# Power_Sheet.net
KiCad netlist of a schematic drawn in Altium Designer
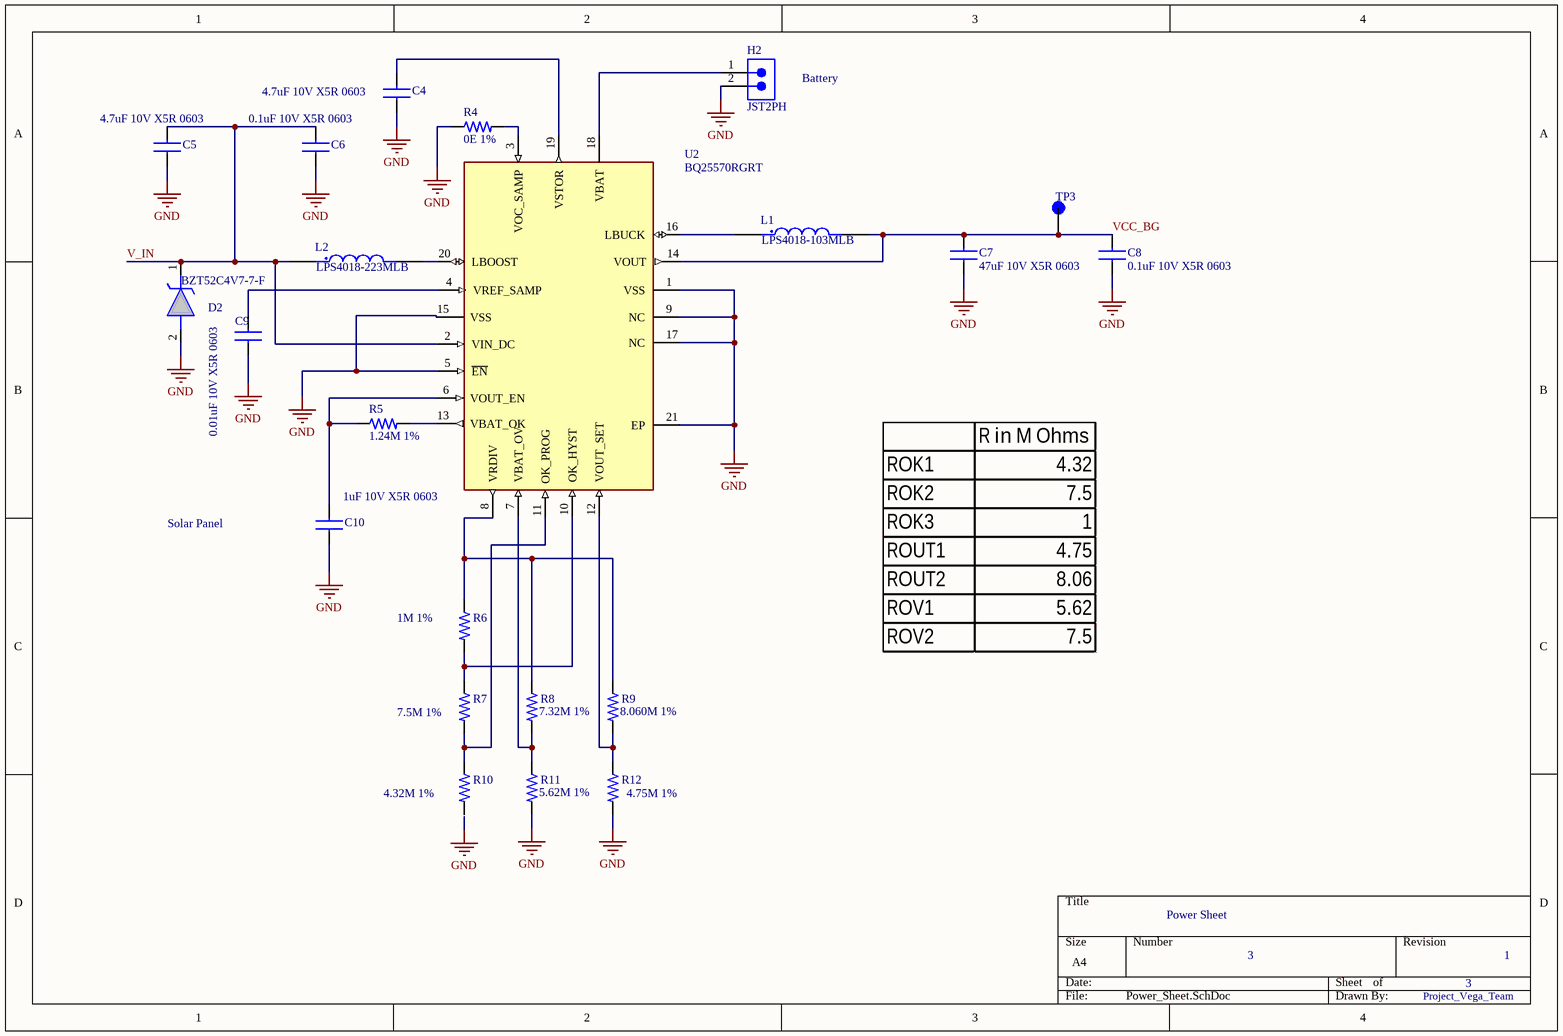
[diagram p0: Power_Sheet.SchDoc]

(export (version "E")
  (design (tool "Eeschema 10.0.6"))
  (components
    (comp (ref "C4")
      (value "4.7uF 10V X5R 0603")
      (footprint "CAP_0603_1MM")
      (description "CAP CER 22UF 10V X5R 0603")
      (fields
        (field (name "MANUFACTURER") "Murata")
        (field (name "MANUFACTURER PART NUMBER") "GRM188R61A226ME15D")
      )
      (libsource (lib "LPEDT_Parts") (part "GRM188R61A226ME15D"))
    )
    (comp (ref "C5")
      (value "4.7uF 10V X5R 0603")
      (footprint "CAP_0603_1MM")
      (description "CAP CER 22UF 10V X5R 0603")
      (fields
        (field (name "MANUFACTURER") "Murata")
        (field (name "MANUFACTURER PART NUMBER") "GRM188R61A226ME15D")
      )
      (libsource (lib "LPEDT_Parts") (part "GRM188R61A226ME15D"))
    )
    (comp (ref "C6")
      (value "0.1uF 10V X5R 0603")
      (footprint "CAP_0603_1MM")
      (description "CAP CER 22UF 10V X5R 0603")
      (fields
        (field (name "MANUFACTURER") "Murata")
        (field (name "MANUFACTURER PART NUMBER") "GRM188R61A226ME15D")
      )
      (libsource (lib "LPEDT_Parts") (part "GRM188R61A226ME15D"))
    )
    (comp (ref "C7")
      (value "47uF 10V X5R 0603")
      (footprint "CAP_0603_1MM")
      (description "CAP CER 22UF 10V X5R 0603")
      (fields
        (field (name "MANUFACTURER") "Murata")
        (field (name "MANUFACTURER PART NUMBER") "GRM188R61A226ME15D")
      )
      (libsource (lib "LPEDT_Parts") (part "GRM188R61A226ME15D"))
    )
    (comp (ref "C8")
      (value "0.1uF 10V X5R 0603")
      (footprint "CAP_0603_1MM")
      (description "CAP CER 22UF 10V X5R 0603")
      (fields
        (field (name "MANUFACTURER") "Murata")
        (field (name "MANUFACTURER PART NUMBER") "GRM188R61A226ME15D")
      )
      (libsource (lib "LPEDT_Parts") (part "GRM188R61A226ME15D"))
    )
    (comp (ref "C9")
      (value "0.01uF 10V X5R 0603")
      (footprint "CAP_0603_1MM")
      (description "CAP CER 22UF 10V X5R 0603")
      (fields
        (field (name "MANUFACTURER") "Murata")
        (field (name "MANUFACTURER PART NUMBER") "GRM188R61A226ME15D")
      )
      (libsource (lib "LPEDT_Parts") (part "GRM188R61A226ME15D"))
    )
    (comp (ref "C10")
      (value "1uF 10V X5R 0603")
      (footprint "CAP_0603_1MM")
      (description "CAP CER 22UF 10V X5R 0603")
      (fields
        (field (name "MANUFACTURER") "Murata")
        (field (name "MANUFACTURER PART NUMBER") "GRM188R61A226ME15D")
      )
      (libsource (lib "LPEDT_Parts") (part "GRM188R61A226ME15D"))
    )
    (comp (ref "D2")
      (value "BZT52C4V7-7-F")
      (footprint "SOD3716X145N")
      (description "Diodes Inc BZT52C4V7-7-F Zener Diode, 4.7V 7% 500 mW SMT 2-Pin SOD-123")
      (fields (field (name "MOUSER PART NUMBER") "621-BZT52C4V7-F"))
      (libsource (lib "BZT52C4V7-7-F") (part "BZT52C4V7-7-F"))
    )
    (comp (ref "H2")
      (value "JST2PH")
      (footprint "JST_B2B-PH-K-S(LF)(SN)")
      (description "Connector Header Through Hole 2 position 0.079\" (2.00mm)")
      (fields (field (name "MANUFACTURER") "JST") (field (name "MANUFACTURER PART NUMBER") "B2B-PH-K-S"))
      (libsource (lib "Connectors") (part "JST2PH"))
    )
    (comp (ref "L1")
      (value "LPS4018-103MLB")
      (footprint "IND_LPS4018-223MRC")
      (description "22 µH Shielded Drum Core Inductor 650 mA 360mOhm Max Nonstandard")
      (fields (field (name "MF") "Coilcraft") (field (name "MP") "LPS4018-223MRC"))
      (libsource (lib "LPS4018-223MRC") (part "LPS4018-223MRC"))
    )
    (comp (ref "L2")
      (value "LPS4018-223MLB")
      (footprint "IND_LPS4018-223MRC")
      (description "22 µH Shielded Drum Core Inductor 650 mA 360mOhm Max Nonstandard")
      (fields (field (name "MF") "Coilcraft") (field (name "MP") "LPS4018-223MRC"))
      (libsource (lib "LPS4018-223MRC") (part "LPS4018-223MRC"))
    )
    (comp (ref "R4")
      (value "0E 1%")
      (footprint "RES_0603_1608X06")
      (description "SMD Chip Resistor, 316 kOhm, ± 1%, 100 mW, 0603 [1608 Metric], Thick Film, General Purpose")
      (fields
        (field (name "MANUFACTURER") "Yageo")
        (field (name "MANUFACTURER PART NUMBER") "RC0603FR-07316KL")
      )
      (libsource (lib "LPEDT_Parts") (part "RC0603FR-07316KL"))
    )
    (comp (ref "R5")
      (value "1.24M 1%")
      (footprint "RES_0603_1608X06")
      (description "SMD Chip Resistor, 316 kOhm, ± 1%, 100 mW, 0603 [1608 Metric], Thick Film, General Purpose")
      (fields
        (field (name "MANUFACTURER") "Yageo")
        (field (name "MANUFACTURER PART NUMBER") "RC0603FR-07316KL")
      )
      (libsource (lib "LPEDT_Parts") (part "RC0603FR-07316KL"))
    )
    (comp (ref "R6")
      (value "1M 1%")
      (footprint "RES_0603_1608X06")
      (description "SMD Chip Resistor, 316 kOhm, ± 1%, 100 mW, 0603 [1608 Metric], Thick Film, General Purpose")
      (fields
        (field (name "MANUFACTURER") "Yageo")
        (field (name "MANUFACTURER PART NUMBER") "RC0603FR-07316KL")
      )
      (libsource (lib "LPEDT_Parts") (part "RC0603FR-07316KL"))
    )
    (comp (ref "R7")
      (value "7.5M 1%")
      (footprint "RES_0603_1608X06")
      (description "SMD Chip Resistor, 316 kOhm, ± 1%, 100 mW, 0603 [1608 Metric], Thick Film, General Purpose")
      (fields
        (field (name "MANUFACTURER") "Yageo")
        (field (name "MANUFACTURER PART NUMBER") "RC0603FR-07316KL")
      )
      (libsource (lib "LPEDT_Parts") (part "RC0603FR-07316KL"))
    )
    (comp (ref "R8")
      (value "7.32M 1%")
      (footprint "RES_0603_1608X06")
      (description "SMD Chip Resistor, 316 kOhm, ± 1%, 100 mW, 0603 [1608 Metric], Thick Film, General Purpose")
      (fields
        (field (name "MANUFACTURER") "Yageo")
        (field (name "MANUFACTURER PART NUMBER") "RC0603FR-07316KL")
      )
      (libsource (lib "LPEDT_Parts") (part "RC0603FR-07316KL"))
    )
    (comp (ref "R9")
      (value "8.060M 1%")
      (footprint "RES_0603_1608X06")
      (description "SMD Chip Resistor, 316 kOhm, ± 1%, 100 mW, 0603 [1608 Metric], Thick Film, General Purpose")
      (fields
        (field (name "MANUFACTURER") "Yageo")
        (field (name "MANUFACTURER PART NUMBER") "RC0603FR-07316KL")
      )
      (libsource (lib "LPEDT_Parts") (part "RC0603FR-07316KL"))
    )
    (comp (ref "R10")
      (value "4.32M 1%")
      (footprint "RES_0603_1608X06")
      (description "SMD Chip Resistor, 316 kOhm, ± 1%, 100 mW, 0603 [1608 Metric], Thick Film, General Purpose")
      (fields
        (field (name "MANUFACTURER") "Yageo")
        (field (name "MANUFACTURER PART NUMBER") "RC0603FR-07316KL")
      )
      (libsource (lib "LPEDT_Parts") (part "RC0603FR-07316KL"))
    )
    (comp (ref "R11")
      (value "5.62M 1%")
      (footprint "RES_0603_1608X06")
      (description "SMD Chip Resistor, 316 kOhm, ± 1%, 100 mW, 0603 [1608 Metric], Thick Film, General Purpose")
      (fields
        (field (name "MANUFACTURER") "Yageo")
        (field (name "MANUFACTURER PART NUMBER") "RC0603FR-07316KL")
      )
      (libsource (lib "LPEDT_Parts") (part "RC0603FR-07316KL"))
    )
    (comp (ref "R12")
      (value "4.75M 1%")
      (footprint "RES_0603_1608X06")
      (description "SMD Chip Resistor, 316 kOhm, ± 1%, 100 mW, 0603 [1608 Metric], Thick Film, General Purpose")
      (fields
        (field (name "MANUFACTURER") "Yageo")
        (field (name "MANUFACTURER PART NUMBER") "RC0603FR-07316KL")
      )
      (libsource (lib "LPEDT_Parts") (part "RC0603FR-07316KL"))
    )
    (comp (ref "TP3")
      (value "Test_point")
      (footprint "TP")
      (description "SMT Test Point- Mininature-1000 pc Reels")
      (fields (field (name "MP") "5019") (field (name "MF") "Keystone Electronics"))
      (libsource (lib "Project_Vega") (part "Test_point"))
    )
    (comp (ref "U2")
      (value "BQ25570RGRT")
      (footprint "QFN50P350X350X100-21N")
      (fields (field (name "MF") "Texas Instruments"))
      (libsource (lib "Project_Vega") (part "BQ25570RGRT"))
    )
  )
  (nets
    (net (code "1") (name "/VCC_BG") (class "Default")
      (node (ref "C7") (pin "2") (pinfunction "2_2") (pintype "passive"))
      (node (ref "C8") (pin "2") (pinfunction "2_2") (pintype "passive"))
      (node (ref "L1") (pin "2") (pinfunction "2_2") (pintype "passive"))
      (node (ref "TP3") (pin "TP") (pinfunction "TP_TP") (pintype "passive"))
      (node (ref "U2") (pin "14") (pinfunction "VOUT_14") (pintype "output"))
    )
    (net (code "2") (name "/V_IN") (class "Default")
      (node (ref "C5") (pin "2") (pinfunction "2_2") (pintype "passive"))
      (node (ref "C6") (pin "2") (pinfunction "2_2") (pintype "passive"))
      (node (ref "D2") (pin "1") (pinfunction "K_1") (pintype "passive"))
      (node (ref "L2") (pin "1") (pinfunction "1_1") (pintype "passive"))
      (node (ref "U2") (pin "2") (pinfunction "VIN_DC_2") (pintype "input"))
    )
    (net (code "3") (name "GND") (class "Default")
      (node (ref "C10") (pin "1") (pinfunction "1_1") (pintype "passive"))
      (node (ref "C4") (pin "1") (pinfunction "1_1") (pintype "passive"))
      (node (ref "C5") (pin "1") (pinfunction "1_1") (pintype "passive"))
      (node (ref "C6") (pin "1") (pinfunction "1_1") (pintype "passive"))
      (node (ref "C7") (pin "1") (pinfunction "1_1") (pintype "passive"))
      (node (ref "C8") (pin "1") (pinfunction "1_1") (pintype "passive"))
      (node (ref "C9") (pin "1") (pinfunction "1_1") (pintype "passive"))
      (node (ref "D2") (pin "2") (pinfunction "A_2") (pintype "passive"))
      (node (ref "H2") (pin "2") (pinfunction "2_2") (pintype "passive"))
      (node (ref "R11") (pin "2") (pinfunction "2_2") (pintype "passive"))
      (node (ref "R12") (pin "2") (pinfunction "2_2") (pintype "passive"))
      (node (ref "R4") (pin "1") (pinfunction "1_1") (pintype "passive"))
      (node (ref "U2") (pin "1") (pinfunction "VSS_1") (pintype "power_in"))
      (node (ref "U2") (pin "15") (pinfunction "VSS_15") (pintype "power_in"))
      (node (ref "U2") (pin "17") (pinfunction "NC_17") (pintype "passive"))
      (node (ref "U2") (pin "21") (pinfunction "EP_21") (pintype "passive"))
      (node (ref "U2") (pin "5") (pinfunction "~{EN}_5") (pintype "input"))
      (node (ref "U2") (pin "9") (pinfunction "NC_9") (pintype "passive"))
    )
    (net (code "4") (name "Net-(U2-LBOOST)") (class "Default")
      (node (ref "L2") (pin "2") (pinfunction "2_2") (pintype "passive"))
      (node (ref "U2") (pin "20") (pinfunction "LBOOST_20") (pintype "bidirectional"))
    )
    (net (code "5") (name "Net-(U2-LBUCK)") (class "Default")
      (node (ref "L1") (pin "1") (pinfunction "1_1") (pintype "passive"))
      (node (ref "U2") (pin "16") (pinfunction "LBUCK_16") (pintype "bidirectional"))
    )
    (net (code "6") (name "Net-(U2-OK_HYST)") (class "Default")
      (node (ref "R6") (pin "2") (pinfunction "2_2") (pintype "passive"))
      (node (ref "R7") (pin "1") (pinfunction "1_1") (pintype "passive"))
      (node (ref "U2") (pin "10") (pinfunction "OK_HYST_10") (pintype "input"))
    )
    (net (code "7") (name "Net-(U2-OK_PROG)") (class "Default")
      (node (ref "R10") (pin "1") (pinfunction "1_1") (pintype "passive"))
      (node (ref "R7") (pin "2") (pinfunction "2_2") (pintype "passive"))
      (node (ref "U2") (pin "11") (pinfunction "OK_PROG_11") (pintype "input"))
    )
    (net (code "8") (name "Net-(U2-VBAT)") (class "Default")
      (node (ref "H2") (pin "1") (pinfunction "1_1") (pintype "passive"))
      (node (ref "U2") (pin "18") (pinfunction "VBAT_18") (pintype "power_in"))
    )
    (net (code "9") (name "Net-(U2-VBAT_OK)") (class "Default")
      (node (ref "R5") (pin "2") (pinfunction "2_2") (pintype "passive"))
      (node (ref "U2") (pin "13") (pinfunction "VBAT_OK_13") (pintype "output"))
    )
    (net (code "10") (name "Net-(U2-VBAT_OV)") (class "Default")
      (node (ref "R11") (pin "1") (pinfunction "1_1") (pintype "passive"))
      (node (ref "R8") (pin "2") (pinfunction "2_2") (pintype "passive"))
      (node (ref "U2") (pin "7") (pinfunction "VBAT_OV_7") (pintype "input"))
    )
    (net (code "11") (name "Net-(U2-VOC_SAMP)") (class "Default")
      (node (ref "R4") (pin "2") (pinfunction "2_2") (pintype "passive"))
      (node (ref "U2") (pin "3") (pinfunction "VOC_SAMP_3") (pintype "input"))
    )
    (net (code "12") (name "Net-(U2-VOUT_EN)") (class "Default")
      (node (ref "C10") (pin "2") (pinfunction "2_2") (pintype "passive"))
      (node (ref "R5") (pin "1") (pinfunction "1_1") (pintype "passive"))
      (node (ref "U2") (pin "6") (pinfunction "VOUT_EN_6") (pintype "input"))
    )
    (net (code "13") (name "Net-(U2-VOUT_SET)") (class "Default")
      (node (ref "R12") (pin "1") (pinfunction "1_1") (pintype "passive"))
      (node (ref "R9") (pin "2") (pinfunction "2_2") (pintype "passive"))
      (node (ref "U2") (pin "12") (pinfunction "VOUT_SET_12") (pintype "input"))
    )
    (net (code "14") (name "Net-(U2-VRDIV)") (class "Default")
      (node (ref "R6") (pin "1") (pinfunction "1_1") (pintype "passive"))
      (node (ref "R8") (pin "1") (pinfunction "1_1") (pintype "passive"))
      (node (ref "R9") (pin "1") (pinfunction "1_1") (pintype "passive"))
      (node (ref "U2") (pin "8") (pinfunction "VRDIV_8") (pintype "output"))
    )
    (net (code "15") (name "Net-(U2-VREF_SAMP)") (class "Default")
      (node (ref "C9") (pin "2") (pinfunction "2_2") (pintype "passive"))
      (node (ref "U2") (pin "4") (pinfunction "VREF_SAMP_4") (pintype "input"))
    )
    (net (code "16") (name "Net-(U2-VSTOR)") (class "Default")
      (node (ref "C4") (pin "2") (pinfunction "2_2") (pintype "passive"))
      (node (ref "U2") (pin "19") (pinfunction "VSTOR_19") (pintype "output"))
    )
    (net (code "17") (name "unconnected-(R10-Pad2)") (class "Default")
      (node (ref "R10") (pin "2") (pinfunction "2_2") (pintype "passive"))
    )
  )
)
